# Alim_1-Redressement_et_Filtrage.net
KiCad netlist of a schematic drawn in EAGLE
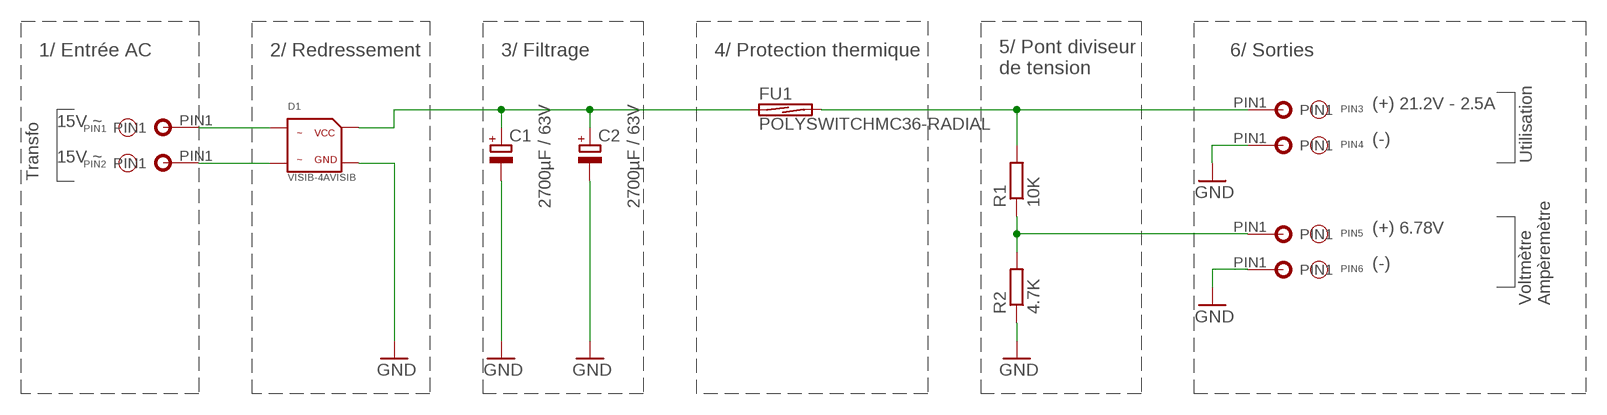
[diagram p0: schematic, sheet 1]

(export (version "E")
  (design (tool "Eeschema 10.0.6"))
  (components
    (comp (ref "C1")
      (value "2700µF / 63V")
      (footprint "eagle-import:EB25D")
      (libsource (lib "eagle-import") (part "CPOL-EUE10-25"))
    )
    (comp (ref "C2")
      (value "2700µF / 63V")
      (footprint "eagle-import:EB25D")
      (libsource (lib "eagle-import") (part "CPOL-EUE10-25"))
    )
    (comp (ref "D1")
      (value "VISIB-4AVISIB")
      (footprint "eagle-import:VISIB-4A")
      (libsource (lib "eagle-import") (part "VISIB-4AVISIB"))
    )
    (comp (ref "FU1")
      (value "POLYSWITCHMC36-RADIAL")
      (footprint "eagle-import:MC36253-RADIAL")
      (libsource (lib "eagle-import") (part "POLYSWITCHMC36-RADIAL"))
    )
    (comp (ref "PIN1")
      (value "CON-FILTRAVERSANT-1FILTRAVERSANT-1")
      (footprint "eagle-import:CON-FILTRAVERSANT-1")
      (libsource (lib "eagle-import") (part "CON-FILTRAVERSANT-1FILTRAVERSANT-1"))
    )
    (comp (ref "PIN2")
      (value "CON-FILTRAVERSANT-1FILTRAVERSANT-1")
      (footprint "eagle-import:CON-FILTRAVERSANT-1")
      (libsource (lib "eagle-import") (part "CON-FILTRAVERSANT-1FILTRAVERSANT-1"))
    )
    (comp (ref "PIN3")
      (value "CON-FILTRAVERSANT-1FILTRAVERSANT-1")
      (footprint "eagle-import:CON-FILTRAVERSANT-1")
      (libsource (lib "eagle-import") (part "CON-FILTRAVERSANT-1FILTRAVERSANT-1"))
    )
    (comp (ref "PIN4")
      (value "CON-FILTRAVERSANT-1FILTRAVERSANT-1")
      (footprint "eagle-import:CON-FILTRAVERSANT-1")
      (libsource (lib "eagle-import") (part "CON-FILTRAVERSANT-1FILTRAVERSANT-1"))
    )
    (comp (ref "PIN5")
      (value "CON-FILTRAVERSANT-1FILTRAVERSANT-1")
      (footprint "eagle-import:CON-FILTRAVERSANT-1")
      (libsource (lib "eagle-import") (part "CON-FILTRAVERSANT-1FILTRAVERSANT-1"))
    )
    (comp (ref "PIN6")
      (value "CON-FILTRAVERSANT-1FILTRAVERSANT-1")
      (footprint "eagle-import:CON-FILTRAVERSANT-1")
      (libsource (lib "eagle-import") (part "CON-FILTRAVERSANT-1FILTRAVERSANT-1"))
    )
    (comp (ref "R1")
      (value "10K")
      (footprint "eagle-import:R0805")
      (libsource (lib "eagle-import") (part "R-EU_R0805"))
    )
    (comp (ref "R2")
      (value "4.7K")
      (footprint "eagle-import:R0805")
      (libsource (lib "eagle-import") (part "R-EU_R0805"))
    )
  )
  (nets
    (net (code "1") (name "GND") (class "Default")
      (node (ref "C1") (pin "-") (pinfunction "-_-") (pintype "passive"))
      (node (ref "C2") (pin "-") (pinfunction "-_-") (pintype "passive"))
      (node (ref "D1") (pin "GND") (pinfunction "GND_GND") (pintype "bidirectional"))
      (node (ref "PIN4") (pin "PIN1") (pinfunction "PIN1_PIN1") (pintype "bidirectional"))
      (node (ref "PIN6") (pin "PIN1") (pinfunction "PIN1_PIN1") (pintype "bidirectional"))
      (node (ref "R2") (pin "1") (pinfunction "1_1") (pintype "passive"))
    )
    (net (code "2") (name "Net-(C1-Pad+)") (class "Default")
      (node (ref "C1") (pin "+") (pinfunction "+_+") (pintype "passive"))
      (node (ref "C2") (pin "+") (pinfunction "+_+") (pintype "passive"))
      (node (ref "D1") (pin "VCC") (pinfunction "VCC_VCC") (pintype "bidirectional"))
      (node (ref "FU1") (pin "1") (pinfunction "1_1") (pintype "passive"))
    )
    (net (code "3") (name "Net-(D1-PadALT1)") (class "Default")
      (node (ref "D1") (pin "ALT1") (pinfunction "ALT1_ALT1") (pintype "bidirectional"))
      (node (ref "PIN1") (pin "PIN1") (pinfunction "PIN1_PIN1") (pintype "bidirectional"))
    )
    (net (code "4") (name "Net-(D1-PadALT2)") (class "Default")
      (node (ref "D1") (pin "ALT2") (pinfunction "ALT2_ALT2") (pintype "bidirectional"))
      (node (ref "PIN2") (pin "PIN1") (pinfunction "PIN1_PIN1") (pintype "bidirectional"))
    )
    (net (code "5") (name "Net-(FU1-Pad2)") (class "Default")
      (node (ref "FU1") (pin "2") (pinfunction "2_2") (pintype "passive"))
      (node (ref "PIN3") (pin "PIN1") (pinfunction "PIN1_PIN1") (pintype "bidirectional"))
      (node (ref "R1") (pin "2") (pinfunction "2_2") (pintype "passive"))
    )
    (net (code "6") (name "Net-(PIN5-PadPIN1)") (class "Default")
      (node (ref "PIN5") (pin "PIN1") (pinfunction "PIN1_PIN1") (pintype "bidirectional"))
      (node (ref "R1") (pin "1") (pinfunction "1_1") (pintype "passive"))
      (node (ref "R2") (pin "2") (pinfunction "2_2") (pintype "passive"))
    )
  )
)
